# gismovii.net
KiCad netlist of a schematic drawn in EAGLE
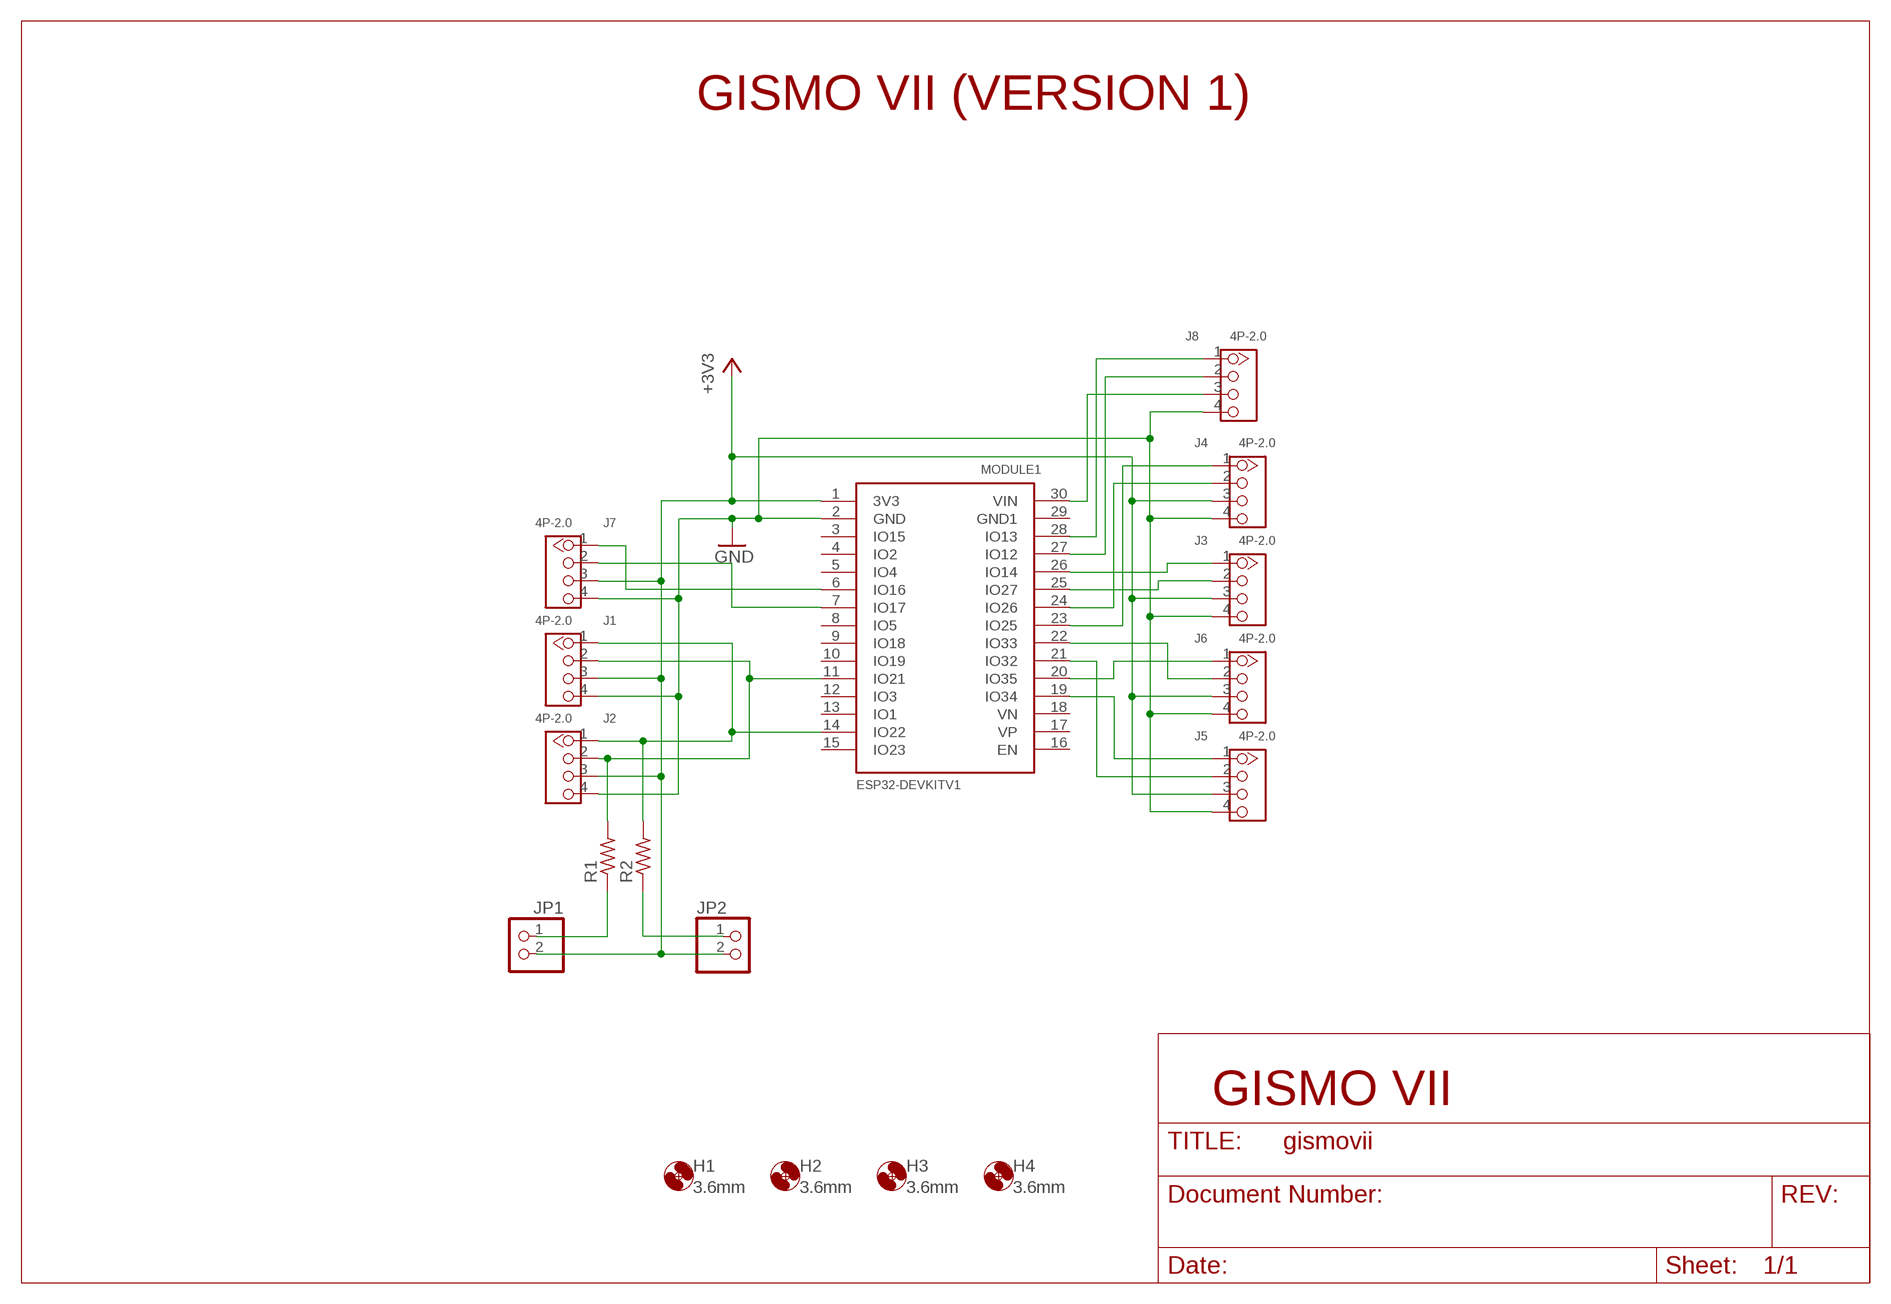
[diagram p0: schematic, sheet 1]

(export (version "E")
  (design (tool "Eeschema 10.0.6"))
  (components
    (comp (ref "H1")
      (value "3.6mm")
      (footprint "eagle-import:3,6")
      (libsource (lib "eagle-import") (part "MOUNT-HOLE3.6"))
    )
    (comp (ref "H2")
      (value "3.6mm")
      (footprint "eagle-import:3,6")
      (libsource (lib "eagle-import") (part "MOUNT-HOLE3.6"))
    )
    (comp (ref "H3")
      (value "3.6mm")
      (footprint "eagle-import:3,6")
      (libsource (lib "eagle-import") (part "MOUNT-HOLE3.6"))
    )
    (comp (ref "H4")
      (value "3.6mm")
      (footprint "eagle-import:3,6")
      (libsource (lib "eagle-import") (part "MOUNT-HOLE3.6"))
    )
    (comp (ref "J1")
      (value "4P-2.0")
      (footprint "eagle-import:HW4-2.0")
      (libsource (lib "eagle-import") (part "GROVE-CONNECTOR-DIP(4P-2.0)"))
    )
    (comp (ref "J2")
      (value "4P-2.0")
      (footprint "eagle-import:HW4-2.0")
      (libsource (lib "eagle-import") (part "GROVE-CONNECTOR-DIP(4P-2.0)"))
    )
    (comp (ref "J3")
      (value "4P-2.0")
      (footprint "eagle-import:HW4-2.0")
      (libsource (lib "eagle-import") (part "GROVE-CONNECTOR-DIP(4P-2.0)"))
    )
    (comp (ref "J4")
      (value "4P-2.0")
      (footprint "eagle-import:HW4-2.0")
      (libsource (lib "eagle-import") (part "GROVE-CONNECTOR-DIP(4P-2.0)"))
    )
    (comp (ref "J5")
      (value "4P-2.0")
      (footprint "eagle-import:HW4-2.0")
      (libsource (lib "eagle-import") (part "GROVE-CONNECTOR-DIP(4P-2.0)"))
    )
    (comp (ref "J6")
      (value "4P-2.0")
      (footprint "eagle-import:HW4-2.0")
      (libsource (lib "eagle-import") (part "GROVE-CONNECTOR-DIP(4P-2.0)"))
    )
    (comp (ref "J7")
      (value "4P-2.0")
      (footprint "eagle-import:HW4-2.0")
      (libsource (lib "eagle-import") (part "GROVE-CONNECTOR-DIP(4P-2.0)"))
    )
    (comp (ref "J8")
      (value "4P-2.0")
      (footprint "eagle-import:HW4-2.0")
      (libsource (lib "eagle-import") (part "GROVE-CONNECTOR-DIP(4P-2.0)"))
    )
    (comp (ref "JP1")
      (value "PINHD-1X2")
      (footprint "eagle-import:1X02")
      (libsource (lib "eagle-import") (part "PINHD-1X2"))
    )
    (comp (ref "JP2")
      (value "PINHD-1X2")
      (footprint "eagle-import:1X02")
      (libsource (lib "eagle-import") (part "PINHD-1X2"))
    )
    (comp (ref "MODULE1")
      (value "ESP32DEVKITV1")
      (footprint "eagle-import:ESP32-DEVKITV1")
      (libsource (lib "eagle-import") (part "ESP32DEVKITV1"))
    )
    (comp (ref "R1")
      (value "R-US_0204/7")
      (footprint "eagle-import:0204_7")
      (libsource (lib "eagle-import") (part "R-US_0204/7"))
    )
    (comp (ref "R2")
      (value "R-US_0204/7")
      (footprint "eagle-import:0204_7")
      (libsource (lib "eagle-import") (part "R-US_0204/7"))
    )
  )
  (nets
    (net (code "1") (name "+3V3") (class "Default")
      (node (ref "J1") (pin "3") (pinfunction "3_3") (pintype "bidirectional"))
      (node (ref "J2") (pin "3") (pinfunction "3_3") (pintype "bidirectional"))
      (node (ref "J3") (pin "3") (pinfunction "3_3") (pintype "bidirectional"))
      (node (ref "J4") (pin "3") (pinfunction "3_3") (pintype "bidirectional"))
      (node (ref "J5") (pin "3") (pinfunction "3_3") (pintype "bidirectional"))
      (node (ref "J6") (pin "3") (pinfunction "3_3") (pintype "bidirectional"))
      (node (ref "J7") (pin "3") (pinfunction "3_3") (pintype "bidirectional"))
      (node (ref "JP1") (pin "2") (pinfunction "2_2") (pintype "passive"))
      (node (ref "JP2") (pin "2") (pinfunction "2_2") (pintype "passive"))
      (node (ref "MODULE1") (pin "1") (pinfunction "3V3_1") (pintype "bidirectional"))
    )
    (net (code "2") (name "GND") (class "Default")
      (node (ref "J1") (pin "4") (pinfunction "4_4") (pintype "bidirectional"))
      (node (ref "J2") (pin "4") (pinfunction "4_4") (pintype "bidirectional"))
      (node (ref "J3") (pin "4") (pinfunction "4_4") (pintype "bidirectional"))
      (node (ref "J4") (pin "4") (pinfunction "4_4") (pintype "bidirectional"))
      (node (ref "J5") (pin "4") (pinfunction "4_4") (pintype "bidirectional"))
      (node (ref "J6") (pin "4") (pinfunction "4_4") (pintype "bidirectional"))
      (node (ref "J7") (pin "4") (pinfunction "4_4") (pintype "bidirectional"))
      (node (ref "J8") (pin "4") (pinfunction "4_4") (pintype "bidirectional"))
      (node (ref "MODULE1") (pin "2") (pinfunction "GND_2") (pintype "bidirectional"))
    )
    (net (code "3") (name "Net-(JP1-Pad1)") (class "Default")
      (node (ref "JP1") (pin "1") (pinfunction "1_1") (pintype "passive"))
      (node (ref "R1") (pin "1") (pinfunction "1_1") (pintype "passive"))
    )
    (net (code "4") (name "Net-(JP2-Pad1)") (class "Default")
      (node (ref "JP2") (pin "1") (pinfunction "1_1") (pintype "passive"))
      (node (ref "R2") (pin "1") (pinfunction "1_1") (pintype "passive"))
    )
    (net (code "5") (name "Net-(MODULE1-IO12)") (class "Default")
      (node (ref "J8") (pin "2") (pinfunction "2_2") (pintype "bidirectional"))
      (node (ref "MODULE1") (pin "27") (pinfunction "IO12_27") (pintype "bidirectional"))
    )
    (net (code "6") (name "Net-(MODULE1-IO13)") (class "Default")
      (node (ref "J8") (pin "1") (pinfunction "1_1") (pintype "bidirectional"))
      (node (ref "MODULE1") (pin "28") (pinfunction "IO13_28") (pintype "bidirectional"))
    )
    (net (code "7") (name "Net-(MODULE1-IO14)") (class "Default")
      (node (ref "J3") (pin "1") (pinfunction "1_1") (pintype "bidirectional"))
      (node (ref "MODULE1") (pin "26") (pinfunction "IO14_26") (pintype "bidirectional"))
    )
    (net (code "8") (name "Net-(MODULE1-IO16)") (class "Default")
      (node (ref "J7") (pin "1") (pinfunction "1_1") (pintype "bidirectional"))
      (node (ref "MODULE1") (pin "6") (pinfunction "IO16_6") (pintype "bidirectional"))
    )
    (net (code "9") (name "Net-(MODULE1-IO17)") (class "Default")
      (node (ref "J7") (pin "2") (pinfunction "2_2") (pintype "bidirectional"))
      (node (ref "MODULE1") (pin "7") (pinfunction "IO17_7") (pintype "bidirectional"))
    )
    (net (code "10") (name "Net-(MODULE1-IO21)") (class "Default")
      (node (ref "J1") (pin "2") (pinfunction "2_2") (pintype "bidirectional"))
      (node (ref "J2") (pin "2") (pinfunction "2_2") (pintype "bidirectional"))
      (node (ref "MODULE1") (pin "11") (pinfunction "IO21_11") (pintype "bidirectional"))
      (node (ref "R1") (pin "2") (pinfunction "2_2") (pintype "passive"))
    )
    (net (code "11") (name "Net-(MODULE1-IO22)") (class "Default")
      (node (ref "J1") (pin "1") (pinfunction "1_1") (pintype "bidirectional"))
      (node (ref "J2") (pin "1") (pinfunction "1_1") (pintype "bidirectional"))
      (node (ref "MODULE1") (pin "14") (pinfunction "IO22_14") (pintype "bidirectional"))
      (node (ref "R2") (pin "2") (pinfunction "2_2") (pintype "passive"))
    )
    (net (code "12") (name "Net-(MODULE1-IO25)") (class "Default")
      (node (ref "J4") (pin "1") (pinfunction "1_1") (pintype "bidirectional"))
      (node (ref "MODULE1") (pin "23") (pinfunction "IO25_23") (pintype "bidirectional"))
    )
    (net (code "13") (name "Net-(MODULE1-IO26)") (class "Default")
      (node (ref "J4") (pin "2") (pinfunction "2_2") (pintype "bidirectional"))
      (node (ref "MODULE1") (pin "24") (pinfunction "IO26_24") (pintype "bidirectional"))
    )
    (net (code "14") (name "Net-(MODULE1-IO27)") (class "Default")
      (node (ref "J3") (pin "2") (pinfunction "2_2") (pintype "bidirectional"))
      (node (ref "MODULE1") (pin "25") (pinfunction "IO27_25") (pintype "bidirectional"))
    )
    (net (code "15") (name "Net-(MODULE1-IO32)") (class "Default")
      (node (ref "J5") (pin "2") (pinfunction "2_2") (pintype "bidirectional"))
      (node (ref "MODULE1") (pin "21") (pinfunction "IO32_21") (pintype "bidirectional"))
    )
    (net (code "16") (name "Net-(MODULE1-IO33)") (class "Default")
      (node (ref "J6") (pin "2") (pinfunction "2_2") (pintype "bidirectional"))
      (node (ref "MODULE1") (pin "22") (pinfunction "IO33_22") (pintype "bidirectional"))
    )
    (net (code "17") (name "Net-(MODULE1-IO34)") (class "Default")
      (node (ref "J5") (pin "1") (pinfunction "1_1") (pintype "bidirectional"))
      (node (ref "MODULE1") (pin "19") (pinfunction "IO34_19") (pintype "bidirectional"))
    )
    (net (code "18") (name "Net-(MODULE1-IO35)") (class "Default")
      (node (ref "J6") (pin "1") (pinfunction "1_1") (pintype "bidirectional"))
      (node (ref "MODULE1") (pin "20") (pinfunction "IO35_20") (pintype "bidirectional"))
    )
    (net (code "19") (name "Net-(MODULE1-VIN)") (class "Default")
      (node (ref "J8") (pin "3") (pinfunction "3_3") (pintype "bidirectional"))
      (node (ref "MODULE1") (pin "30") (pinfunction "VIN_30") (pintype "bidirectional"))
    )
    (net (code "20") (name "unconnected-(MODULE1-EN-Pad16)") (class "Default")
      (node (ref "MODULE1") (pin "16") (pinfunction "EN_16") (pintype "bidirectional"))
    )
    (net (code "21") (name "unconnected-(MODULE1-GND1-Pad29)") (class "Default")
      (node (ref "MODULE1") (pin "29") (pinfunction "GND1_29") (pintype "bidirectional"))
    )
    (net (code "22") (name "unconnected-(MODULE1-IO1-Pad13)") (class "Default")
      (node (ref "MODULE1") (pin "13") (pinfunction "IO1_13") (pintype "bidirectional"))
    )
    (net (code "23") (name "unconnected-(MODULE1-IO2-Pad4)") (class "Default")
      (node (ref "MODULE1") (pin "4") (pinfunction "IO2_4") (pintype "bidirectional"))
    )
    (net (code "24") (name "unconnected-(MODULE1-IO3-Pad12)") (class "Default")
      (node (ref "MODULE1") (pin "12") (pinfunction "IO3_12") (pintype "bidirectional"))
    )
    (net (code "25") (name "unconnected-(MODULE1-IO4-Pad5)") (class "Default")
      (node (ref "MODULE1") (pin "5") (pinfunction "IO4_5") (pintype "bidirectional"))
    )
    (net (code "26") (name "unconnected-(MODULE1-IO5-Pad8)") (class "Default")
      (node (ref "MODULE1") (pin "8") (pinfunction "IO5_8") (pintype "bidirectional"))
    )
    (net (code "27") (name "unconnected-(MODULE1-IO15-Pad3)") (class "Default")
      (node (ref "MODULE1") (pin "3") (pinfunction "IO15_3") (pintype "bidirectional"))
    )
    (net (code "28") (name "unconnected-(MODULE1-IO18-Pad9)") (class "Default")
      (node (ref "MODULE1") (pin "9") (pinfunction "IO18_9") (pintype "bidirectional"))
    )
    (net (code "29") (name "unconnected-(MODULE1-IO19-Pad10)") (class "Default")
      (node (ref "MODULE1") (pin "10") (pinfunction "IO19_10") (pintype "bidirectional"))
    )
    (net (code "30") (name "unconnected-(MODULE1-IO23-Pad15)") (class "Default")
      (node (ref "MODULE1") (pin "15") (pinfunction "IO23_15") (pintype "bidirectional"))
    )
    (net (code "31") (name "unconnected-(MODULE1-VN-Pad18)") (class "Default")
      (node (ref "MODULE1") (pin "18") (pinfunction "VN_18") (pintype "bidirectional"))
    )
    (net (code "32") (name "unconnected-(MODULE1-VP-Pad17)") (class "Default")
      (node (ref "MODULE1") (pin "17") (pinfunction "VP_17") (pintype "bidirectional"))
    )
  )
)
